# acciedent_vehicle__located_based_on_gps_.net
KiCad netlist of a schematic drawn in EAGLE
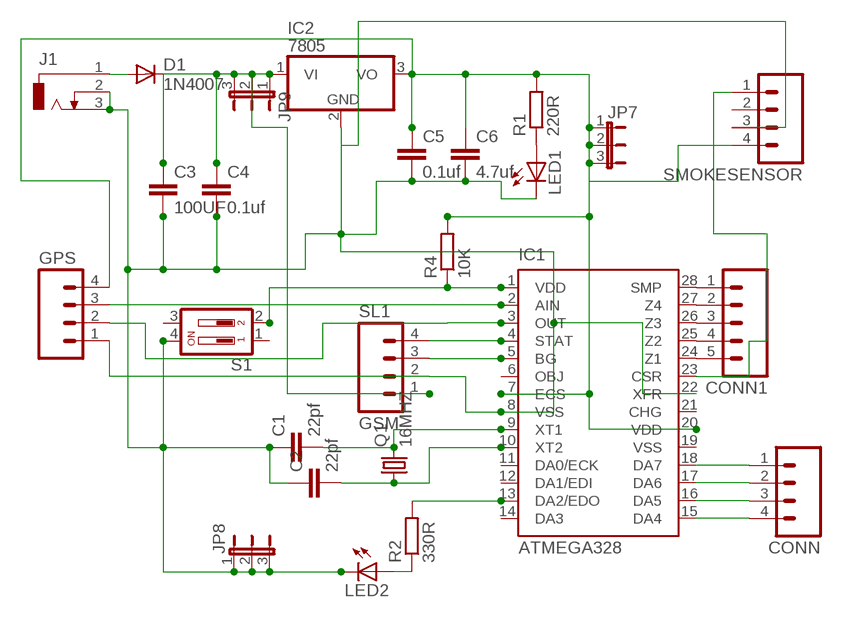
[diagram p0: schematic, sheet 1]

(export (version "E")
  (design (tool "Eeschema 10.0.6"))
  (components
    (comp (ref "C1")
      (value "22pf")
      (footprint "eagle-import:C2.5-2")
      (libsource (lib "eagle-import") (part "C2.5/2"))
    )
    (comp (ref "C2")
      (value "22pf")
      (footprint "eagle-import:C2.5-2")
      (libsource (lib "eagle-import") (part "C2.5/2"))
    )
    (comp (ref "C3")
      (value "100UF")
      (footprint "eagle-import:C2.5-2")
      (libsource (lib "eagle-import") (part "C2.5/2"))
    )
    (comp (ref "C4")
      (value "0.1uf")
      (footprint "eagle-import:C2.5-2")
      (libsource (lib "eagle-import") (part "C2.5/2"))
    )
    (comp (ref "C5")
      (value "0.1uf")
      (footprint "eagle-import:C2.5-2")
      (libsource (lib "eagle-import") (part "C2.5/2"))
    )
    (comp (ref "C6")
      (value "4.7uf")
      (footprint "eagle-import:C2.5-2")
      (libsource (lib "eagle-import") (part "C2.5/2"))
    )
    (comp (ref "CONN")
      (value "M04")
      (footprint "eagle-import:04P")
      (fields (field (name "OC_FARNELL") "unknown") (field (name "OC_NEWARK") "unknown"))
      (libsource (lib "eagle-import") (part "M04"))
    )
    (comp (ref "CONN1")
      (value "M05")
      (footprint "eagle-import:05P")
      (libsource (lib "eagle-import") (part "M05"))
    )
    (comp (ref "D1")
      (value "1N4007")
      (footprint "eagle-import:DO41-10")
      (libsource (lib "eagle-import") (part "1N4004"))
    )
    (comp (ref "GPS")
      (value "M04")
      (footprint "eagle-import:04P")
      (fields (field (name "OC_FARNELL") "unknown") (field (name "OC_NEWARK") "unknown"))
      (libsource (lib "eagle-import") (part "M04"))
    )
    (comp (ref "IC1")
      (value "ATMEGA328")
      (footprint "eagle-import:DIL28-3")
      (libsource (lib "eagle-import") (part "QT9701BD"))
    )
    (comp (ref "IC2")
      (value "7805")
      (footprint "eagle-import:TO220V")
      (libsource (lib "eagle-import") (part "78TV6"))
    )
    (comp (ref "J1")
      (value "DCJ0303")
      (footprint "eagle-import:DCJ0303")
      (libsource (lib "eagle-import") (part "DCJ0303"))
    )
    (comp (ref "JP7")
      (value "JP2E")
      (footprint "eagle-import:JP2")
      (libsource (lib "eagle-import") (part "JP2E"))
    )
    (comp (ref "JP8")
      (value "JP2E")
      (footprint "eagle-import:JP2")
      (libsource (lib "eagle-import") (part "JP2E"))
    )
    (comp (ref "JP9")
      (value "JP2E")
      (footprint "eagle-import:JP2")
      (libsource (lib "eagle-import") (part "JP2E"))
    )
    (comp (ref "LED1")
      (value "LED3MM")
      (footprint "eagle-import:LED3MM")
      (libsource (lib "eagle-import") (part "LED3MM"))
    )
    (comp (ref "LED2")
      (value "LED3MM")
      (footprint "eagle-import:LED3MM")
      (libsource (lib "eagle-import") (part "LED3MM"))
    )
    (comp (ref "Q1")
      (value "16MHZ")
      (footprint "eagle-import:HC49_S")
      (libsource (lib "eagle-import") (part "CRYSTALHC49S"))
    )
    (comp (ref "R1")
      (value "220R")
      (footprint "eagle-import:0207_10")
      (libsource (lib "eagle-import") (part "R-EU_0207/10"))
    )
    (comp (ref "R2")
      (value "330R")
      (footprint "eagle-import:0207_10")
      (libsource (lib "eagle-import") (part "R-EU_0207/10"))
    )
    (comp (ref "R4")
      (value "10K")
      (footprint "eagle-import:0207_10")
      (libsource (lib "eagle-import") (part "R-EU_0207/10"))
    )
    (comp (ref "S1")
      (value "DP02")
      (footprint "eagle-import:DP-02")
      (fields (field (name "MPN") "MCDP02"))
      (libsource (lib "eagle-import") (part "DP02"))
    )
    (comp (ref "SL1")
      (value "GSM")
      (footprint "eagle-import:04P")
      (libsource (lib "eagle-import") (part "M04"))
    )
    (comp (ref "SMOKESENSOR")
      (value "M04")
      (footprint "eagle-import:04P")
      (libsource (lib "eagle-import") (part "M04"))
    )
  )
  (nets
    (net (code "1") (name "Net-(D1-PadA)") (class "Default")
      (node (ref "D1") (pin "A") (pinfunction "A_A") (pintype "passive"))
      (node (ref "J1") (pin "1") (pinfunction "1_1") (pintype "passive"))
    )
    (net (code "2") (name "Net-(IC1-AIN)") (class "Default")
      (node (ref "GPS") (pin "3") (pinfunction "3_3") (pintype "passive"))
      (node (ref "IC1") (pin "2") (pinfunction "AIN_2") (pintype "input"))
    )
    (net (code "3") (name "Net-(IC1-BG)") (class "Default")
      (node (ref "IC1") (pin "5") (pinfunction "BG_5") (pintype "input"))
      (node (ref "SL1") (pin "3") (pinfunction "3_3") (pintype "passive"))
    )
    (net (code "4") (name "Net-(IC1-CSR)") (class "Default")
      (node (ref "IC1") (pin "23") (pinfunction "CSR_23") (pintype "output"))
      (node (ref "SMOKESENSOR") (pin "1") (pinfunction "1_1") (pintype "passive"))
    )
    (net (code "5") (name "Net-(IC1-DA2{slash}EDO)") (class "Default")
      (node (ref "IC1") (pin "13") (pinfunction "DA2/EDO_13") (pintype "output"))
      (node (ref "R2") (pin "2") (pinfunction "2_2") (pintype "passive"))
    )
    (net (code "6") (name "Net-(IC1-DA4)") (class "Default")
      (node (ref "CONN") (pin "4") (pinfunction "4_4") (pintype "passive"))
      (node (ref "IC1") (pin "15") (pinfunction "DA4_15") (pintype "output"))
    )
    (net (code "7") (name "Net-(IC1-DA5)") (class "Default")
      (node (ref "CONN") (pin "3") (pinfunction "3_3") (pintype "passive"))
      (node (ref "IC1") (pin "16") (pinfunction "DA5_16") (pintype "output"))
    )
    (net (code "8") (name "Net-(IC1-DA6)") (class "Default")
      (node (ref "CONN") (pin "2") (pinfunction "2_2") (pintype "passive"))
      (node (ref "IC1") (pin "17") (pinfunction "DA6_17") (pintype "output"))
    )
    (net (code "9") (name "Net-(IC1-DA7)") (class "Default")
      (node (ref "CONN") (pin "1") (pinfunction "1_1") (pintype "passive"))
      (node (ref "IC1") (pin "18") (pinfunction "DA7_18") (pintype "output"))
    )
    (net (code "10") (name "Net-(IC1-ECS)") (class "Default")
      (node (ref "C5") (pin "1") (pinfunction "1_1") (pintype "passive"))
      (node (ref "C6") (pin "1") (pinfunction "1_1") (pintype "passive"))
      (node (ref "GPS") (pin "4") (pinfunction "4_4") (pintype "passive"))
      (node (ref "IC1") (pin "20") (pinfunction "VDD_20") (pintype "input"))
      (node (ref "IC1") (pin "7") (pinfunction "ECS_7") (pintype "output"))
      (node (ref "IC2") (pin "3") (pinfunction "VO_3") (pintype "passive"))
      (node (ref "JP7") (pin "1") (pinfunction "1_1") (pintype "passive"))
      (node (ref "JP7") (pin "2") (pinfunction "2_2") (pintype "passive"))
      (node (ref "JP7") (pin "3") (pinfunction "3_3") (pintype "passive"))
      (node (ref "R1") (pin "2") (pinfunction "2_2") (pintype "passive"))
      (node (ref "R4") (pin "2") (pinfunction "2_2") (pintype "passive"))
      (node (ref "SMOKESENSOR") (pin "4") (pinfunction "4_4") (pintype "passive"))
    )
    (net (code "11") (name "Net-(IC1-OUT)") (class "Default")
      (node (ref "GPS") (pin "2") (pinfunction "2_2") (pintype "passive"))
      (node (ref "IC1") (pin "3") (pinfunction "OUT_3") (pintype "output"))
    )
    (net (code "12") (name "Net-(IC1-SMP)") (class "Default")
      (node (ref "CONN1") (pin "1") (pinfunction "1_1") (pintype "passive"))
      (node (ref "IC1") (pin "28") (pinfunction "SMP_28") (pintype "output"))
    )
    (net (code "13") (name "Net-(IC1-STAT)") (class "Default")
      (node (ref "IC1") (pin "4") (pinfunction "STAT_4") (pintype "output"))
      (node (ref "SL1") (pin "4") (pinfunction "4_4") (pintype "passive"))
    )
    (net (code "14") (name "Net-(IC1-VDD-Pad1)") (class "Default")
      (node (ref "IC1") (pin "1") (pinfunction "VDD_1") (pintype "input"))
      (node (ref "R4") (pin "1") (pinfunction "1_1") (pintype "passive"))
      (node (ref "S1") (pin "2") (pinfunction "2_2") (pintype "passive"))
    )
    (net (code "15") (name "Net-(IC1-XFR)") (class "Default")
      (node (ref "C1") (pin "1") (pinfunction "1_1") (pintype "passive"))
      (node (ref "C2") (pin "1") (pinfunction "1_1") (pintype "passive"))
      (node (ref "C3") (pin "2") (pinfunction "2_2") (pintype "passive"))
      (node (ref "C4") (pin "2") (pinfunction "2_2") (pintype "passive"))
      (node (ref "C5") (pin "2") (pinfunction "2_2") (pintype "passive"))
      (node (ref "C6") (pin "2") (pinfunction "2_2") (pintype "passive"))
      (node (ref "GPS") (pin "1") (pinfunction "1_1") (pintype "passive"))
      (node (ref "IC1") (pin "22") (pinfunction "XFR_22") (pintype "output"))
      (node (ref "IC1") (pin "8") (pinfunction "VSS_8") (pintype "input"))
      (node (ref "IC2") (pin "2") (pinfunction "GND_2") (pintype "passive"))
      (node (ref "J1") (pin "2") (pinfunction "2_2") (pintype "passive"))
      (node (ref "J1") (pin "3") (pinfunction "3_3") (pintype "passive"))
      (node (ref "JP8") (pin "1") (pinfunction "1_1") (pintype "passive"))
      (node (ref "JP8") (pin "2") (pinfunction "2_2") (pintype "passive"))
      (node (ref "JP8") (pin "3") (pinfunction "3_3") (pintype "passive"))
      (node (ref "LED1") (pin "K") (pinfunction "C_K") (pintype "passive"))
      (node (ref "LED2") (pin "K") (pinfunction "C_K") (pintype "passive"))
      (node (ref "S1") (pin "4") (pinfunction "4_4") (pintype "passive"))
      (node (ref "SL1") (pin "2") (pinfunction "2_2") (pintype "passive"))
      (node (ref "SMOKESENSOR") (pin "3") (pinfunction "3_3") (pintype "passive"))
    )
    (net (code "16") (name "Net-(IC1-XT1)") (class "Default")
      (node (ref "C1") (pin "2") (pinfunction "2_2") (pintype "passive"))
      (node (ref "IC1") (pin "9") (pinfunction "XT1_9") (pintype "input"))
      (node (ref "Q1") (pin "2") (pinfunction "2_2") (pintype "passive"))
    )
    (net (code "17") (name "Net-(IC1-XT2)") (class "Default")
      (node (ref "C2") (pin "2") (pinfunction "2_2") (pintype "passive"))
      (node (ref "IC1") (pin "10") (pinfunction "XT2_10") (pintype "output"))
      (node (ref "Q1") (pin "1") (pinfunction "1_1") (pintype "passive"))
    )
    (net (code "18") (name "Net-(IC1-Z1)") (class "Default")
      (node (ref "CONN1") (pin "5") (pinfunction "5_5") (pintype "passive"))
      (node (ref "IC1") (pin "24") (pinfunction "Z1_24") (pintype "output"))
    )
    (net (code "19") (name "Net-(IC1-Z2)") (class "Default")
      (node (ref "CONN1") (pin "4") (pinfunction "4_4") (pintype "passive"))
      (node (ref "IC1") (pin "25") (pinfunction "Z2_25") (pintype "output"))
    )
    (net (code "20") (name "Net-(IC1-Z3)") (class "Default")
      (node (ref "CONN1") (pin "3") (pinfunction "3_3") (pintype "passive"))
      (node (ref "IC1") (pin "26") (pinfunction "Z3_26") (pintype "output"))
    )
    (net (code "21") (name "Net-(IC1-Z4)") (class "Default")
      (node (ref "CONN1") (pin "2") (pinfunction "2_2") (pintype "passive"))
      (node (ref "IC1") (pin "27") (pinfunction "Z4_27") (pintype "output"))
    )
    (net (code "22") (name "Net-(IC2-VI)") (class "Default")
      (node (ref "C3") (pin "1") (pinfunction "1_1") (pintype "passive"))
      (node (ref "C4") (pin "1") (pinfunction "1_1") (pintype "passive"))
      (node (ref "D1") (pin "C") (pinfunction "C_C") (pintype "passive"))
      (node (ref "IC2") (pin "1") (pinfunction "VI_1") (pintype "input"))
      (node (ref "JP9") (pin "1") (pinfunction "1_1") (pintype "passive"))
      (node (ref "JP9") (pin "2") (pinfunction "2_2") (pintype "passive"))
      (node (ref "JP9") (pin "3") (pinfunction "3_3") (pintype "passive"))
      (node (ref "SL1") (pin "1") (pinfunction "1_1") (pintype "passive"))
    )
    (net (code "23") (name "Net-(LED1-PadA)") (class "Default")
      (node (ref "LED1") (pin "A") (pinfunction "A_A") (pintype "passive"))
      (node (ref "R1") (pin "1") (pinfunction "1_1") (pintype "passive"))
    )
    (net (code "24") (name "Net-(LED2-PadA)") (class "Default")
      (node (ref "LED2") (pin "A") (pinfunction "A_A") (pintype "passive"))
      (node (ref "R2") (pin "1") (pinfunction "1_1") (pintype "passive"))
    )
    (net (code "25") (name "unconnected-(IC1-CHG-Pad21)") (class "Default")
      (node (ref "IC1") (pin "21") (pinfunction "CHG_21") (pintype "output"))
    )
    (net (code "26") (name "unconnected-(IC1-DA0{slash}ECK-Pad11)") (class "Default")
      (node (ref "IC1") (pin "11") (pinfunction "DA0/ECK_11") (pintype "output"))
    )
    (net (code "27") (name "unconnected-(IC1-DA1{slash}EDI-Pad12)") (class "Default")
      (node (ref "IC1") (pin "12") (pinfunction "DA1/EDI_12") (pintype "output"))
    )
    (net (code "28") (name "unconnected-(IC1-DA3-Pad14)") (class "Default")
      (node (ref "IC1") (pin "14") (pinfunction "DA3_14") (pintype "output"))
    )
    (net (code "29") (name "unconnected-(IC1-OBJ-Pad6)") (class "Default")
      (node (ref "IC1") (pin "6") (pinfunction "OBJ_6") (pintype "input"))
    )
    (net (code "30") (name "unconnected-(IC1-VSS-Pad19)") (class "Default")
      (node (ref "IC1") (pin "19") (pinfunction "VSS_19") (pintype "input"))
    )
    (net (code "31") (name "unconnected-(S1-Pad1)") (class "Default")
      (node (ref "S1") (pin "1") (pinfunction "1_1") (pintype "passive"))
    )
    (net (code "32") (name "unconnected-(S1-Pad3)") (class "Default")
      (node (ref "S1") (pin "3") (pinfunction "3_3") (pintype "passive"))
    )
    (net (code "33") (name "unconnected-(SMOKESENSOR-Pad2)") (class "Default")
      (node (ref "SMOKESENSOR") (pin "2") (pinfunction "2_2") (pintype "passive"))
    )
  )
)
